# PCB-JOY1.net
KiCad netlist of a schematic drawn in EAGLE
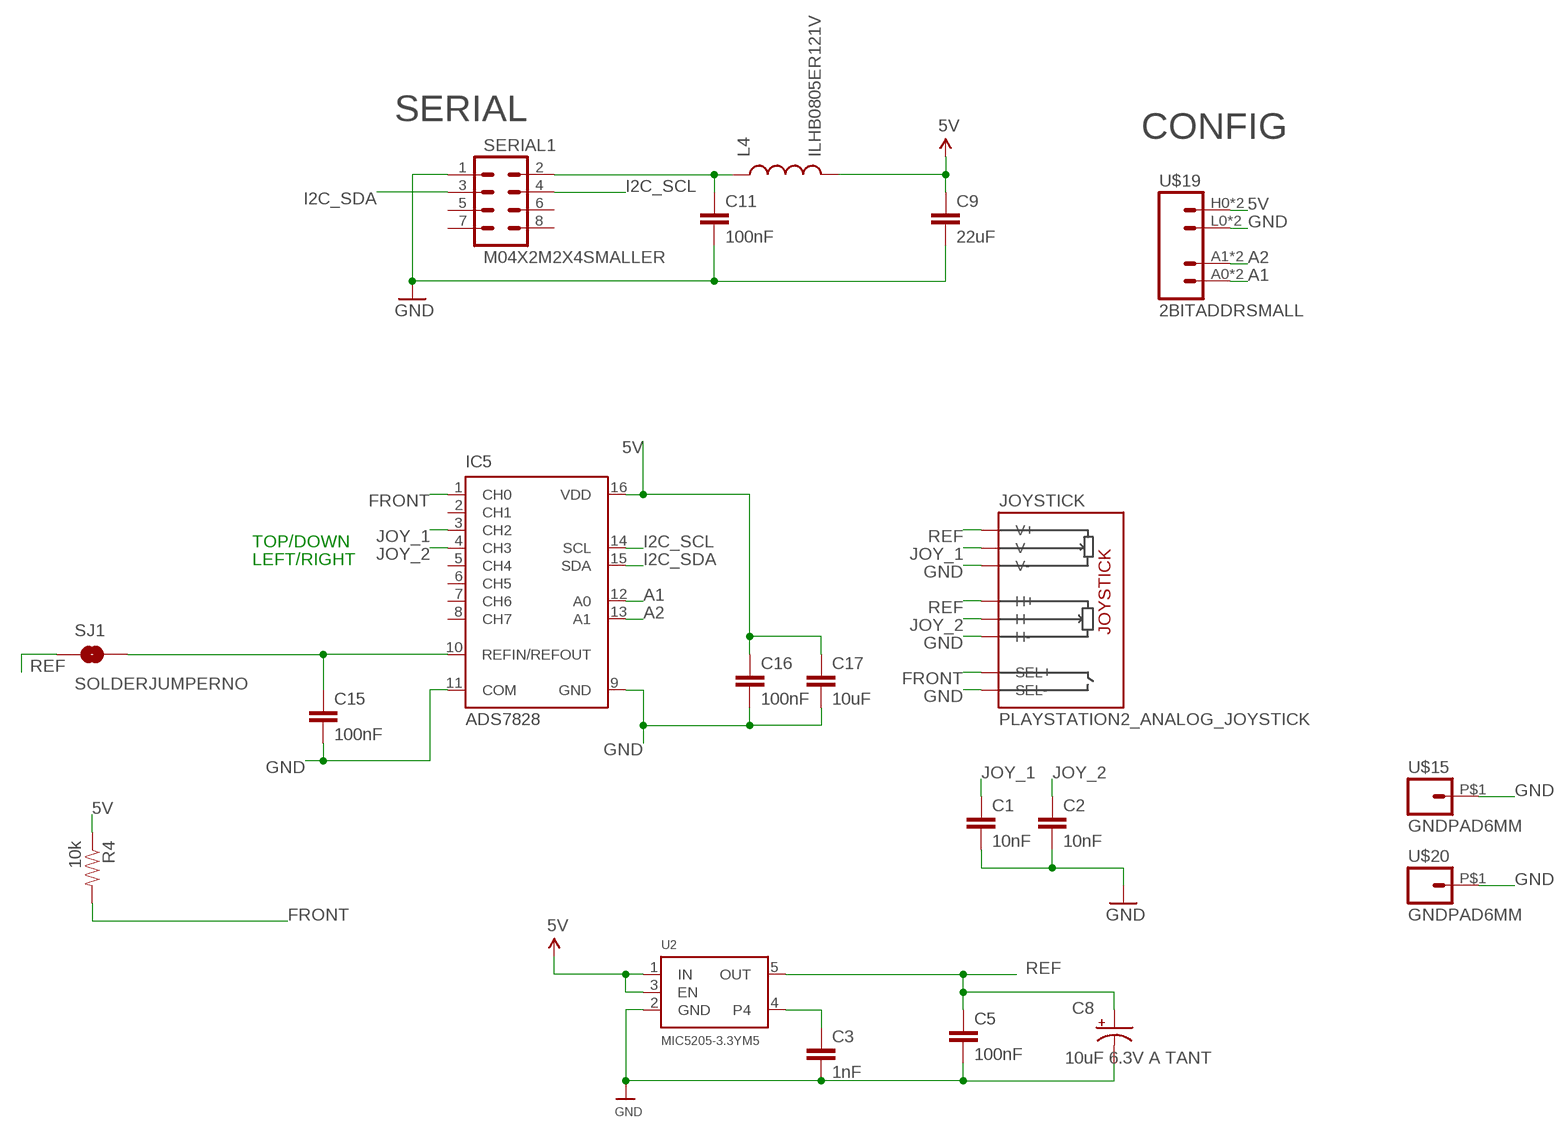
[diagram p0: schematic, sheet 1]

(export (version "E")
  (design (tool "Eeschema 10.0.6"))
  (components
    (comp (ref "C1")
      (value "10nF")
      (footprint "eagle-import:0603-CAP")
      (libsource (lib "eagle-import") (part "CAP0603-CAP"))
    )
    (comp (ref "C2")
      (value "10nF")
      (footprint "eagle-import:0603-CAP")
      (libsource (lib "eagle-import") (part "CAP0603-CAP"))
    )
    (comp (ref "C3")
      (value "1nF")
      (footprint "eagle-import:0603-CAP")
      (libsource (lib "eagle-import") (part "CAP0603-CAP"))
    )
    (comp (ref "C5")
      (value "100nF")
      (footprint "eagle-import:0603-CAP")
      (libsource (lib "eagle-import") (part "CAP0603-CAP"))
    )
    (comp (ref "C8")
      (value "10uF 6.3V A TANT")
      (footprint "eagle-import:EIA3216")
      (libsource (lib "eagle-import") (part "CAP_POL1206"))
    )
    (comp (ref "C9")
      (value "22uF")
      (footprint "eagle-import:0805")
      (libsource (lib "eagle-import") (part "CAP0805"))
    )
    (comp (ref "C11")
      (value "100nF")
      (footprint "eagle-import:0603-CAP")
      (libsource (lib "eagle-import") (part "CAP0603-CAP"))
    )
    (comp (ref "C15")
      (value "100nF")
      (footprint "eagle-import:0603-CAP")
      (libsource (lib "eagle-import") (part "CAP0603-CAP"))
    )
    (comp (ref "C16")
      (value "100nF")
      (footprint "eagle-import:0603-CAP")
      (libsource (lib "eagle-import") (part "CAP0603-CAP"))
    )
    (comp (ref "C17")
      (value "10uF")
      (footprint "eagle-import:0805")
      (libsource (lib "eagle-import") (part "CAP0805"))
    )
    (comp (ref "IC5")
      (value "ADS7828")
      (footprint "eagle-import:TSSOP16-PW")
      (fields (field (name "MF") "TEXAS INSTRUMENTS") (field (name "MPN") "ADS7828E/250"))
      (libsource (lib "eagle-import") (part "ADS7828"))
    )
    (comp (ref "JOYSTICK")
      (value "PLAYSTATION2_ANALOG_JOYSTICK")
      (footprint "eagle-import:PLAYSTATION2_ANALOG_JOYSTICK")
      (libsource (lib "eagle-import") (part "PLAYSTATION2_ANALOG_JOYSTICK"))
    )
    (comp (ref "L4")
      (value "ILHB0805ER121V")
      (footprint "eagle-import:0805")
      (libsource (lib "eagle-import") (part "INDUCTOR0805"))
    )
    (comp (ref "R4")
      (value "10k")
      (footprint "eagle-import:0603-RES")
      (libsource (lib "eagle-import") (part "RESISTOR0603-RES"))
    )
    (comp (ref "SERIAL1")
      (value "M04X2M2X4SMALLER")
      (footprint "eagle-import:M2X4SMALLER")
      (libsource (lib "eagle-import") (part "M04X2M2X4SMALLER"))
    )
    (comp (ref "SJ1")
      (value "SOLDERJUMPERNO")
      (footprint "eagle-import:SJ_2S-NO")
      (libsource (lib "eagle-import") (part "SOLDERJUMPERNO"))
    )
    (comp (ref "U$15")
      (value "GNDPAD6MM")
      (footprint "eagle-import:3.2MMPAD6MM")
      (libsource (lib "eagle-import") (part "GNDPAD6MM"))
    )
    (comp (ref "U$19")
      (value "2BITADDRSMALL")
      (footprint "eagle-import:2BITADDR_SMALL")
      (libsource (lib "eagle-import") (part "2BITADDRSMALL"))
    )
    (comp (ref "U$20")
      (value "GNDPAD6MM")
      (footprint "eagle-import:3.2MMPAD6MM")
      (libsource (lib "eagle-import") (part "GNDPAD6MM"))
    )
    (comp (ref "U2")
      (value "MIC5205-3.3YM5")
      (footprint "eagle-import:SOT23-5")
      (libsource (lib "eagle-import") (part "VREG_SOT23-5"))
    )
  )
  (nets
    (net (code "1") (name "/A1") (class "Default")
      (node (ref "IC5") (pin "12") (pinfunction "A0_12") (pintype "input"))
      (node (ref "U$19") (pin "A0") (pinfunction "A1_A0") (pintype "passive"))
      (node (ref "U$19") (pin "AS0") (pinfunction "A1_AS0") (pintype "passive"))
    )
    (net (code "2") (name "/A2") (class "Default")
      (node (ref "IC5") (pin "13") (pinfunction "A1_13") (pintype "input"))
      (node (ref "U$19") (pin "A1") (pinfunction "A2_A1") (pintype "passive"))
      (node (ref "U$19") (pin "AS1") (pinfunction "A2_AS1") (pintype "passive"))
    )
    (net (code "3") (name "/FRONT") (class "Default")
      (node (ref "IC5") (pin "1") (pinfunction "CH0_1") (pintype "input"))
      (node (ref "JOYSTICK") (pin "B1A") (pinfunction "SEL+_B1A") (pintype "bidirectional"))
      (node (ref "R4") (pin "2") (pinfunction "2_2") (pintype "passive"))
    )
    (net (code "4") (name "/I2C_SCL") (class "Default")
      (node (ref "IC5") (pin "14") (pinfunction "SCL_14") (pintype "input"))
      (node (ref "SERIAL1") (pin "4") (pinfunction "4_4") (pintype "passive"))
    )
    (net (code "5") (name "/I2C_SDA") (class "Default")
      (node (ref "IC5") (pin "15") (pinfunction "SDA_15") (pintype "bidirectional"))
      (node (ref "SERIAL1") (pin "3") (pinfunction "3_3") (pintype "passive"))
    )
    (net (code "6") (name "/JOY_1") (class "Default")
      (node (ref "C1") (pin "1") (pinfunction "1_1") (pintype "passive"))
      (node (ref "IC5") (pin "3") (pinfunction "CH2_3") (pintype "input"))
      (node (ref "JOYSTICK") (pin "V2") (pinfunction "V_V2") (pintype "bidirectional"))
    )
    (net (code "7") (name "/JOY_2") (class "Default")
      (node (ref "C2") (pin "1") (pinfunction "1_1") (pintype "passive"))
      (node (ref "IC5") (pin "4") (pinfunction "CH3_4") (pintype "input"))
      (node (ref "JOYSTICK") (pin "H2") (pinfunction "H_H2") (pintype "bidirectional"))
    )
    (net (code "8") (name "/REF") (class "Default")
      (node (ref "C5") (pin "1") (pinfunction "1_1") (pintype "passive"))
      (node (ref "C8") (pin "A") (pinfunction "+_A") (pintype "passive"))
      (node (ref "JOYSTICK") (pin "H1") (pinfunction "H+_H1") (pintype "bidirectional"))
      (node (ref "JOYSTICK") (pin "V1") (pinfunction "V+_V1") (pintype "bidirectional"))
      (node (ref "SJ1") (pin "1") (pinfunction "1_1") (pintype "passive"))
      (node (ref "U2") (pin "5") (pinfunction "OUT_5") (pintype "bidirectional"))
    )
    (net (code "9") (name "5V") (class "Default")
      (node (ref "C16") (pin "1") (pinfunction "1_1") (pintype "passive"))
      (node (ref "C17") (pin "1") (pinfunction "1_1") (pintype "passive"))
      (node (ref "C9") (pin "1") (pinfunction "1_1") (pintype "passive"))
      (node (ref "IC5") (pin "16") (pinfunction "VDD_16") (pintype "power_in"))
      (node (ref "L4") (pin "2") (pinfunction "2_2") (pintype "passive"))
      (node (ref "R4") (pin "1") (pinfunction "1_1") (pintype "passive"))
      (node (ref "U$19") (pin "H0") (pinfunction "VCC_H0") (pintype "passive"))
      (node (ref "U$19") (pin "H1") (pinfunction "VCC_H1") (pintype "passive"))
      (node (ref "U2") (pin "1") (pinfunction "IN_1") (pintype "bidirectional"))
      (node (ref "U2") (pin "3") (pinfunction "EN_3") (pintype "bidirectional"))
    )
    (net (code "10") (name "GND") (class "Default")
      (node (ref "C1") (pin "2") (pinfunction "2_2") (pintype "passive"))
      (node (ref "C11") (pin "2") (pinfunction "2_2") (pintype "passive"))
      (node (ref "C15") (pin "2") (pinfunction "2_2") (pintype "passive"))
      (node (ref "C16") (pin "2") (pinfunction "2_2") (pintype "passive"))
      (node (ref "C17") (pin "2") (pinfunction "2_2") (pintype "passive"))
      (node (ref "C2") (pin "2") (pinfunction "2_2") (pintype "passive"))
      (node (ref "C3") (pin "2") (pinfunction "2_2") (pintype "passive"))
      (node (ref "C5") (pin "2") (pinfunction "2_2") (pintype "passive"))
      (node (ref "C8") (pin "C") (pinfunction "-_C") (pintype "passive"))
      (node (ref "C9") (pin "2") (pinfunction "2_2") (pintype "passive"))
      (node (ref "IC5") (pin "11") (pinfunction "COM_11") (pintype "input"))
      (node (ref "IC5") (pin "9") (pinfunction "GND_9") (pintype "power_in"))
      (node (ref "JOYSTICK") (pin "B2A") (pinfunction "SEL-_B2A") (pintype "bidirectional"))
      (node (ref "JOYSTICK") (pin "H3") (pinfunction "H-_H3") (pintype "bidirectional"))
      (node (ref "JOYSTICK") (pin "V3") (pinfunction "V-_V3") (pintype "bidirectional"))
      (node (ref "SERIAL1") (pin "1") (pinfunction "1_1") (pintype "passive"))
      (node (ref "U$15") (pin "P$1") (pinfunction "1_P$1") (pintype "passive"))
      (node (ref "U$19") (pin "L0") (pinfunction "GND_L0") (pintype "passive"))
      (node (ref "U$19") (pin "L1") (pinfunction "GND_L1") (pintype "passive"))
      (node (ref "U$20") (pin "P$1") (pinfunction "1_P$1") (pintype "passive"))
      (node (ref "U2") (pin "2") (pinfunction "GND_2") (pintype "bidirectional"))
    )
    (net (code "11") (name "Net-(C11-Pad1)") (class "Default")
      (node (ref "C11") (pin "1") (pinfunction "1_1") (pintype "passive"))
      (node (ref "L4") (pin "1") (pinfunction "1_1") (pintype "passive"))
      (node (ref "SERIAL1") (pin "2") (pinfunction "2_2") (pintype "passive"))
    )
    (net (code "12") (name "Net-(IC5-REFIN{slash}REFOUT)") (class "Default")
      (node (ref "C15") (pin "1") (pinfunction "1_1") (pintype "passive"))
      (node (ref "IC5") (pin "10") (pinfunction "REFIN/REFOUT_10") (pintype "passive"))
      (node (ref "SJ1") (pin "2") (pinfunction "2_2") (pintype "passive"))
    )
    (net (code "13") (name "Net-(U2-P4)") (class "Default")
      (node (ref "C3") (pin "1") (pinfunction "1_1") (pintype "passive"))
      (node (ref "U2") (pin "4") (pinfunction "P4_4") (pintype "bidirectional"))
    )
    (net (code "14") (name "unconnected-(IC5-CH1-Pad2)") (class "Default")
      (node (ref "IC5") (pin "2") (pinfunction "CH1_2") (pintype "input"))
    )
    (net (code "15") (name "unconnected-(IC5-CH4-Pad5)") (class "Default")
      (node (ref "IC5") (pin "5") (pinfunction "CH4_5") (pintype "input"))
    )
    (net (code "16") (name "unconnected-(IC5-CH5-Pad6)") (class "Default")
      (node (ref "IC5") (pin "6") (pinfunction "CH5_6") (pintype "input"))
    )
    (net (code "17") (name "unconnected-(IC5-CH6-Pad7)") (class "Default")
      (node (ref "IC5") (pin "7") (pinfunction "CH6_7") (pintype "input"))
    )
    (net (code "18") (name "unconnected-(IC5-CH7-Pad8)") (class "Default")
      (node (ref "IC5") (pin "8") (pinfunction "CH7_8") (pintype "input"))
    )
    (net (code "19") (name "unconnected-(SERIAL1-Pad5)") (class "Default")
      (node (ref "SERIAL1") (pin "5") (pinfunction "5_5") (pintype "passive"))
    )
    (net (code "20") (name "unconnected-(SERIAL1-Pad6)") (class "Default")
      (node (ref "SERIAL1") (pin "6") (pinfunction "6_6") (pintype "passive"))
    )
    (net (code "21") (name "unconnected-(SERIAL1-Pad7)") (class "Default")
      (node (ref "SERIAL1") (pin "7") (pinfunction "7_7") (pintype "passive"))
    )
    (net (code "22") (name "unconnected-(SERIAL1-Pad8)") (class "Default")
      (node (ref "SERIAL1") (pin "8") (pinfunction "8_8") (pintype "passive"))
    )
  )
)
